# main.net
KiCad netlist of a schematic drawn in EAGLE
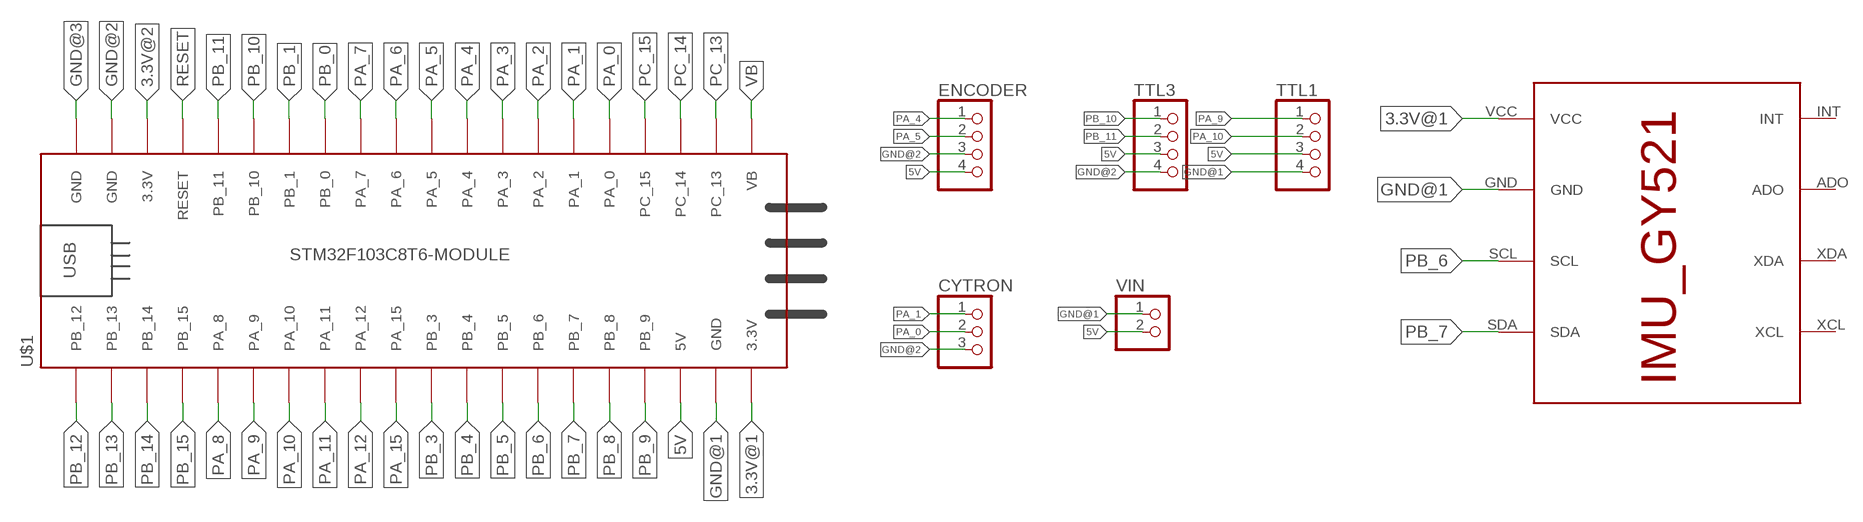
[diagram p0: schematic, sheet 1]

(export (version "E")
  (design (tool "Eeschema 10.0.6"))
  (components
    (comp (ref "CYTRON")
      (value "PINHD-3_DATA")
      (footprint "eagle-import:1X03_DATA")
      (libsource (lib "eagle-import") (part "PINHD-3_DATA"))
    )
    (comp (ref "ENCODER")
      (value "PINHD-4_DATA")
      (footprint "eagle-import:1X04_DATA")
      (libsource (lib "eagle-import") (part "PINHD-4_DATA"))
    )
    (comp (ref "IMU")
      (value "IMU_ROBOCON_GY521")
      (footprint "eagle-import:IMU_GY521")
      (libsource (lib "eagle-import") (part "IMU_ROBOCON_GY521"))
    )
    (comp (ref "TTL1")
      (value "PINHD-4_DATA")
      (footprint "eagle-import:1X04_DATA")
      (libsource (lib "eagle-import") (part "PINHD-4_DATA"))
    )
    (comp (ref "TTL3")
      (value "PINHD-4_DATA")
      (footprint "eagle-import:1X04_DATA")
      (libsource (lib "eagle-import") (part "PINHD-4_DATA"))
    )
    (comp (ref "U$1")
      (value "STM32F103C8T6-MODULE")
      (footprint "eagle-import:STM32F103C8T6-MODULE")
      (libsource (lib "eagle-import") (part "STM32F103C8T6-MODULE"))
    )
    (comp (ref "VIN")
      (value "PINHD-2_DATA")
      (footprint "eagle-import:1X02_DATA")
      (libsource (lib "eagle-import") (part "PINHD-2_DATA"))
    )
  )
  (nets
    (net (code "1") (name "3.3V@1") (class "Default")
      (node (ref "IMU") (pin "VCC") (pinfunction "VCC_VCC") (pintype "bidirectional"))
      (node (ref "U$1") (pin "3.3V_1") (pinfunction "3.3V_3.3V_1") (pintype "bidirectional"))
    )
    (net (code "2") (name "3.3V@2") (class "Default")
      (node (ref "U$1") (pin "3.3V_2") (pinfunction "3.3V_3.3V_2") (pintype "bidirectional"))
    )
    (net (code "3") (name "5V") (class "Default")
      (node (ref "ENCODER") (pin "4") (pinfunction "4_4") (pintype "passive"))
      (node (ref "TTL1") (pin "3") (pinfunction "3_3") (pintype "passive"))
      (node (ref "TTL3") (pin "3") (pinfunction "3_3") (pintype "passive"))
      (node (ref "U$1") (pin "5V") (pinfunction "5V_5V") (pintype "bidirectional"))
      (node (ref "VIN") (pin "2") (pinfunction "2_2") (pintype "passive"))
    )
    (net (code "4") (name "GND@1") (class "Default")
      (node (ref "IMU") (pin "GND") (pinfunction "GND_GND") (pintype "bidirectional"))
      (node (ref "TTL1") (pin "4") (pinfunction "4_4") (pintype "passive"))
      (node (ref "U$1") (pin "GND_1") (pinfunction "GND_GND_1") (pintype "bidirectional"))
      (node (ref "VIN") (pin "1") (pinfunction "1_1") (pintype "passive"))
    )
    (net (code "5") (name "GND@2") (class "Default")
      (node (ref "CYTRON") (pin "3") (pinfunction "3_3") (pintype "passive"))
      (node (ref "ENCODER") (pin "3") (pinfunction "3_3") (pintype "passive"))
      (node (ref "TTL3") (pin "4") (pinfunction "4_4") (pintype "passive"))
      (node (ref "U$1") (pin "GND_2") (pinfunction "GND_GND_2") (pintype "bidirectional"))
    )
    (net (code "6") (name "GND@3") (class "Default")
      (node (ref "U$1") (pin "GND_3") (pinfunction "GND_GND_3") (pintype "power_in"))
    )
    (net (code "7") (name "PA_0") (class "Default")
      (node (ref "CYTRON") (pin "2") (pinfunction "2_2") (pintype "passive"))
      (node (ref "U$1") (pin "PA_0") (pinfunction "PA_0_PA_0") (pintype "bidirectional"))
    )
    (net (code "8") (name "PA_1") (class "Default")
      (node (ref "CYTRON") (pin "1") (pinfunction "1_1") (pintype "passive"))
      (node (ref "U$1") (pin "PA_1") (pinfunction "PA_1_PA_1") (pintype "bidirectional"))
    )
    (net (code "9") (name "PA_2") (class "Default")
      (node (ref "U$1") (pin "PA_2") (pinfunction "PA_2_PA_2") (pintype "bidirectional"))
    )
    (net (code "10") (name "PA_3") (class "Default")
      (node (ref "U$1") (pin "PA_3") (pinfunction "PA_3_PA_3") (pintype "bidirectional"))
    )
    (net (code "11") (name "PA_4") (class "Default")
      (node (ref "ENCODER") (pin "1") (pinfunction "1_1") (pintype "passive"))
      (node (ref "U$1") (pin "PA_4") (pinfunction "PA_4_PA_4") (pintype "bidirectional"))
    )
    (net (code "12") (name "PA_5") (class "Default")
      (node (ref "ENCODER") (pin "2") (pinfunction "2_2") (pintype "passive"))
      (node (ref "U$1") (pin "PA_5") (pinfunction "PA_5_PA_5") (pintype "bidirectional"))
    )
    (net (code "13") (name "PA_6") (class "Default")
      (node (ref "U$1") (pin "PA_6") (pinfunction "PA_6_PA_6") (pintype "bidirectional"))
    )
    (net (code "14") (name "PA_7") (class "Default")
      (node (ref "U$1") (pin "PA_7") (pinfunction "PA_7_PA_7") (pintype "bidirectional"))
    )
    (net (code "15") (name "PA_8") (class "Default")
      (node (ref "U$1") (pin "PA_8") (pinfunction "PA_8_PA_8") (pintype "bidirectional"))
    )
    (net (code "16") (name "PA_9") (class "Default")
      (node (ref "TTL1") (pin "1") (pinfunction "1_1") (pintype "passive"))
      (node (ref "U$1") (pin "PA_9") (pinfunction "PA_9_PA_9") (pintype "bidirectional"))
    )
    (net (code "17") (name "PA_10") (class "Default")
      (node (ref "TTL1") (pin "2") (pinfunction "2_2") (pintype "passive"))
      (node (ref "U$1") (pin "PA_10") (pinfunction "PA_10_PA_10") (pintype "bidirectional"))
    )
    (net (code "18") (name "PA_11") (class "Default")
      (node (ref "U$1") (pin "PA_11") (pinfunction "PA_11_PA_11") (pintype "bidirectional"))
    )
    (net (code "19") (name "PA_12") (class "Default")
      (node (ref "U$1") (pin "PA_12") (pinfunction "PA_12_PA_12") (pintype "bidirectional"))
    )
    (net (code "20") (name "PA_15") (class "Default")
      (node (ref "U$1") (pin "PA_15") (pinfunction "PA_15_PA_15") (pintype "bidirectional"))
    )
    (net (code "21") (name "PB_0") (class "Default")
      (node (ref "U$1") (pin "PB_0") (pinfunction "PB_0_PB_0") (pintype "bidirectional"))
    )
    (net (code "22") (name "PB_1") (class "Default")
      (node (ref "U$1") (pin "PB_1") (pinfunction "PB_1_PB_1") (pintype "bidirectional"))
    )
    (net (code "23") (name "PB_3") (class "Default")
      (node (ref "U$1") (pin "PB_3") (pinfunction "PB_3_PB_3") (pintype "bidirectional"))
    )
    (net (code "24") (name "PB_4") (class "Default")
      (node (ref "U$1") (pin "PB_4") (pinfunction "PB_4_PB_4") (pintype "bidirectional"))
    )
    (net (code "25") (name "PB_5") (class "Default")
      (node (ref "U$1") (pin "PB_5") (pinfunction "PB_5_PB_5") (pintype "bidirectional"))
    )
    (net (code "26") (name "PB_6") (class "Default")
      (node (ref "IMU") (pin "SCL") (pinfunction "SCL_SCL") (pintype "bidirectional"))
      (node (ref "U$1") (pin "PB_6") (pinfunction "PB_6_PB_6") (pintype "bidirectional"))
    )
    (net (code "27") (name "PB_7") (class "Default")
      (node (ref "IMU") (pin "SDA") (pinfunction "SDA_SDA") (pintype "bidirectional"))
      (node (ref "U$1") (pin "PB_7") (pinfunction "PB_7_PB_7") (pintype "bidirectional"))
    )
    (net (code "28") (name "PB_8") (class "Default")
      (node (ref "U$1") (pin "PB_8") (pinfunction "PB_8_PB_8") (pintype "bidirectional"))
    )
    (net (code "29") (name "PB_9") (class "Default")
      (node (ref "U$1") (pin "PB_9") (pinfunction "PB_9_PB_9") (pintype "bidirectional"))
    )
    (net (code "30") (name "PB_10") (class "Default")
      (node (ref "TTL3") (pin "1") (pinfunction "1_1") (pintype "passive"))
      (node (ref "U$1") (pin "PB_10") (pinfunction "PB_10_PB_10") (pintype "bidirectional"))
    )
    (net (code "31") (name "PB_11") (class "Default")
      (node (ref "TTL3") (pin "2") (pinfunction "2_2") (pintype "passive"))
      (node (ref "U$1") (pin "PB_11") (pinfunction "PB_11_PB_11") (pintype "bidirectional"))
    )
    (net (code "32") (name "PB_12") (class "Default")
      (node (ref "U$1") (pin "PB_12") (pinfunction "PB_12_PB_12") (pintype "bidirectional"))
    )
    (net (code "33") (name "PB_13") (class "Default")
      (node (ref "U$1") (pin "PB_13") (pinfunction "PB_13_PB_13") (pintype "bidirectional"))
    )
    (net (code "34") (name "PB_14") (class "Default")
      (node (ref "U$1") (pin "PB_14") (pinfunction "PB_14_PB_14") (pintype "bidirectional"))
    )
    (net (code "35") (name "PB_15") (class "Default")
      (node (ref "U$1") (pin "PB_15") (pinfunction "PB_15_PB_15") (pintype "bidirectional"))
    )
    (net (code "36") (name "PC_13") (class "Default")
      (node (ref "U$1") (pin "PC_13") (pinfunction "PC_13_PC_13") (pintype "bidirectional"))
    )
    (net (code "37") (name "PC_14") (class "Default")
      (node (ref "U$1") (pin "PC_14") (pinfunction "PC_14_PC_14") (pintype "bidirectional"))
    )
    (net (code "38") (name "PC_15") (class "Default")
      (node (ref "U$1") (pin "PC_15") (pinfunction "PC_15_PC_15") (pintype "bidirectional"))
    )
    (net (code "39") (name "RESET") (class "Default")
      (node (ref "U$1") (pin "RESET") (pinfunction "RESET_RESET") (pintype "bidirectional"))
    )
    (net (code "40") (name "VB") (class "Default")
      (node (ref "U$1") (pin "VB") (pinfunction "VB_VB") (pintype "bidirectional"))
    )
    (net (code "41") (name "unconnected-(IMU-PadADO)") (class "Default")
      (node (ref "IMU") (pin "ADO") (pinfunction "ADO_ADO") (pintype "bidirectional"))
    )
    (net (code "42") (name "unconnected-(IMU-PadINT)") (class "Default")
      (node (ref "IMU") (pin "INT") (pinfunction "INT_INT") (pintype "bidirectional"))
    )
    (net (code "43") (name "unconnected-(IMU-PadXCL)") (class "Default")
      (node (ref "IMU") (pin "XCL") (pinfunction "XCL_XCL") (pintype "bidirectional"))
    )
    (net (code "44") (name "unconnected-(IMU-PadXDA)") (class "Default")
      (node (ref "IMU") (pin "XDA") (pinfunction "XDA_XDA") (pintype "bidirectional"))
    )
  )
)
